# 6_ALARM.net
KiCad netlist of a schematic drawn in Altium Designer
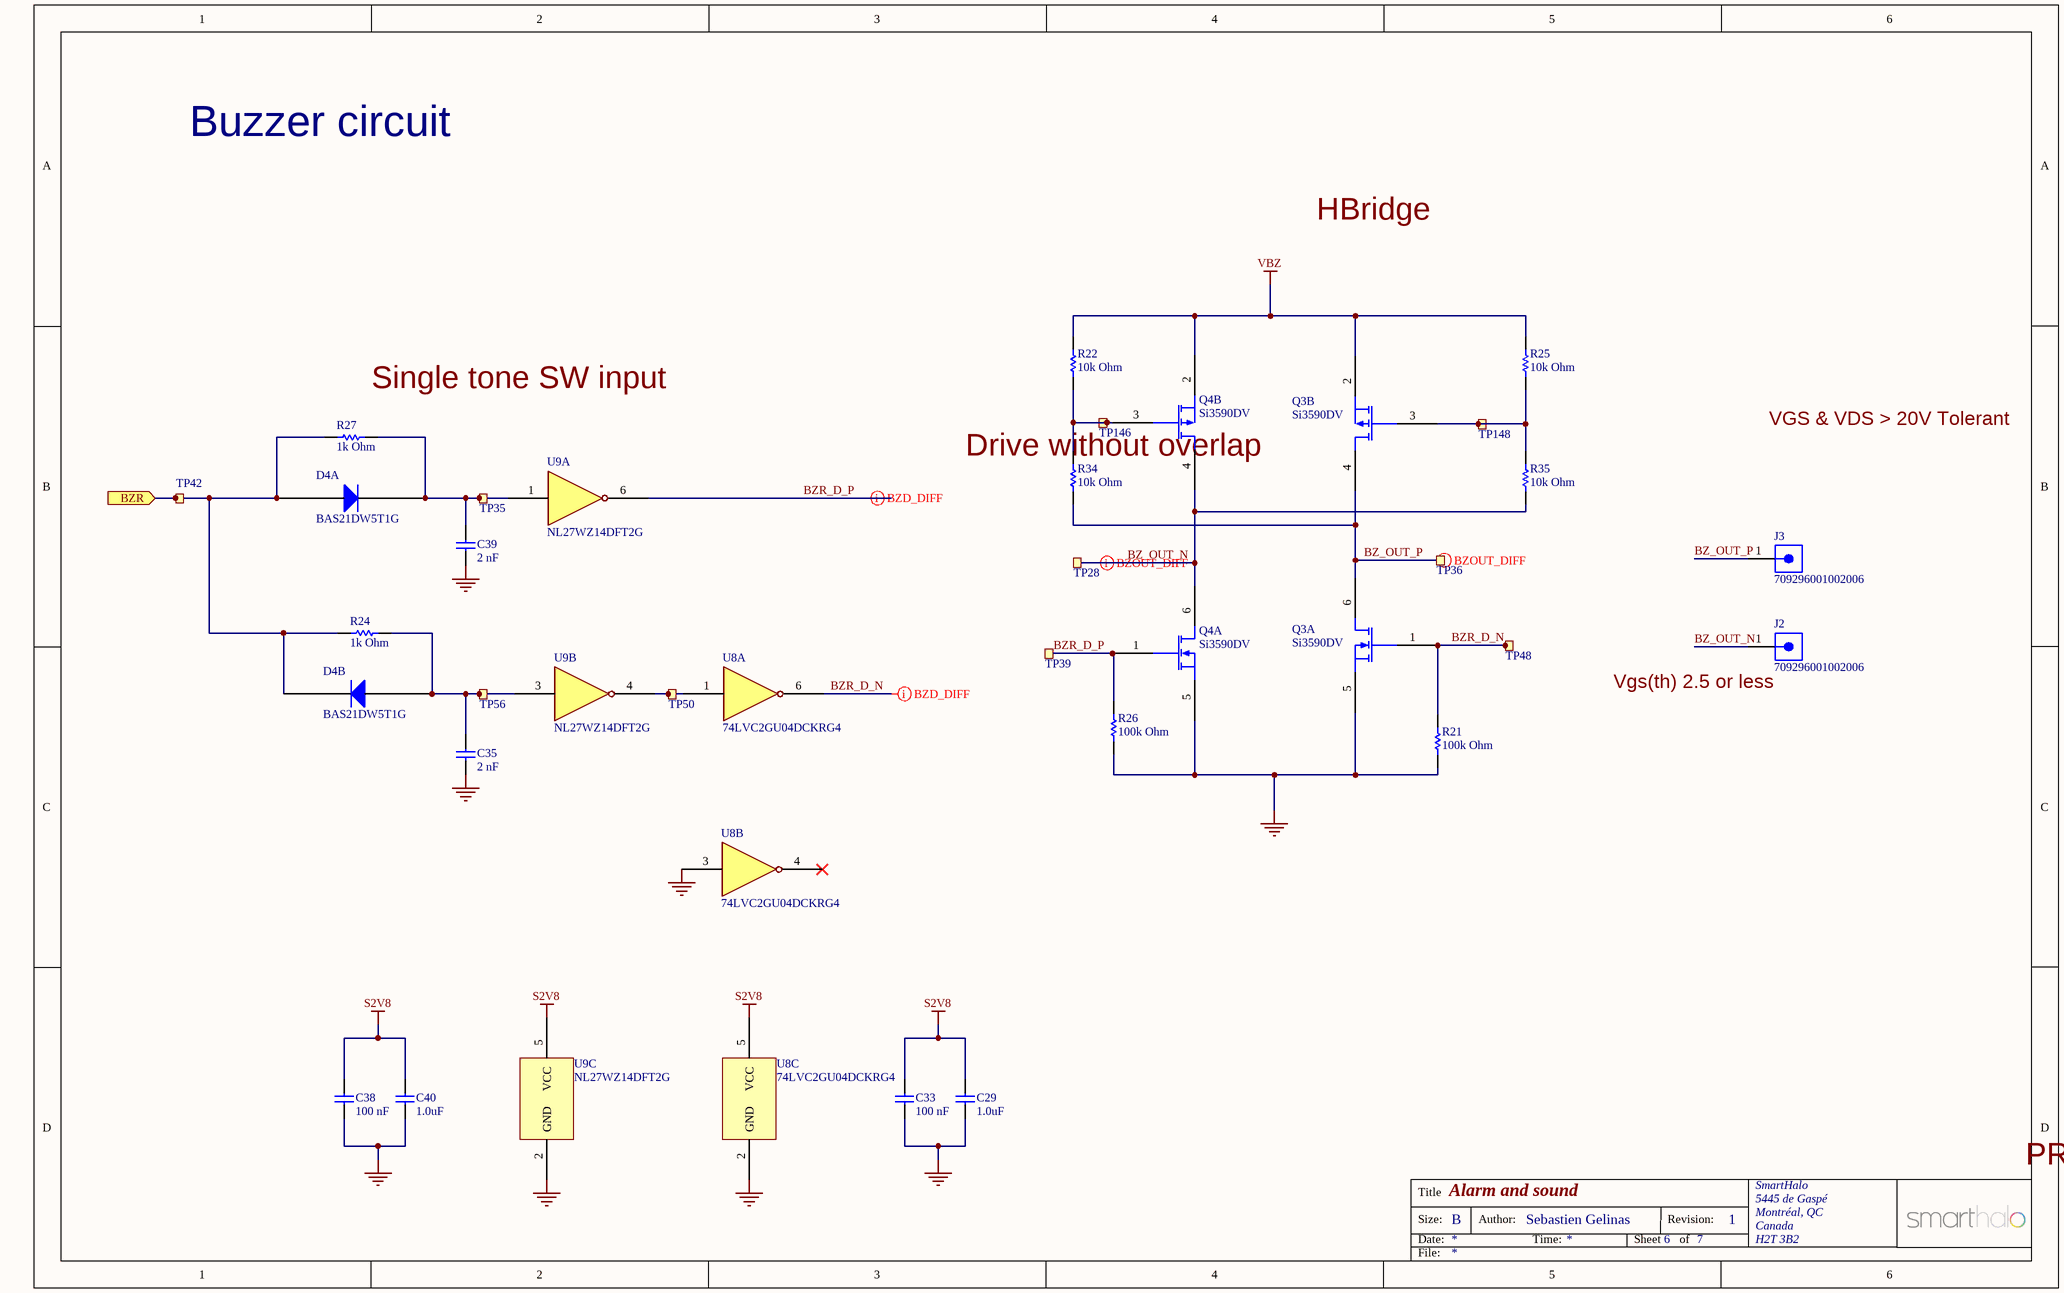
[diagram p0: 6_ALARM.SchDoc]

(export (version "E")
  (design (tool "Eeschema 10.0.6"))
  (components
    (comp (ref "C29")
      (value "1.0uF")
      (footprint "Varitron_CAP0603")
      (description "1uF 10V X7R 10% 0603 (1608 Metric)  SMD")
      (fields (field (name "TOLERANCE") "10%"))
      (libsource (lib "SmartHalo") (part "Varitron_CAP0603"))
    )
    (comp (ref "C33")
      (value "100 nF")
      (footprint "Varitron_CAP0402")
      (description "100 nF 10V X7R 10% 0402 (1005 Metric)  SMD")
      (fields (field (name "TOLERANCE") "10%"))
      (libsource (lib "SmartHalo") (part "Varitron_CAP0402"))
    )
    (comp (ref "C35")
      (value "2 nF")
      (footprint "Varitron_CAP0402")
      (description "2 nF 6V X5R 10% 0402 (1005 Metric)  SMD")
      (fields (field (name "TOLERANCE") "10%"))
      (libsource (lib "SmartHalo") (part "Varitron_CAP0402"))
    )
    (comp (ref "C38")
      (value "100 nF")
      (footprint "Varitron_CAP0402")
      (description "100 nF 10V X7R 10% 0402 (1005 Metric)  SMD")
      (fields (field (name "TOLERANCE") "10%"))
      (libsource (lib "SmartHalo") (part "Varitron_CAP0402"))
    )
    (comp (ref "C39")
      (value "2 nF")
      (footprint "Varitron_CAP0402")
      (description "2 nF 6V X5R 10% 0402 (1005 Metric)  SMD")
      (fields (field (name "TOLERANCE") "10%"))
      (libsource (lib "SmartHalo") (part "Varitron_CAP0402"))
    )
    (comp (ref "C40")
      (value "1.0uF")
      (footprint "Varitron_CAP0603")
      (description "1uF 10V X7R 10% 0603 (1608 Metric)  SMD")
      (fields (field (name "TOLERANCE") "10%"))
      (libsource (lib "SmartHalo") (part "Varitron_CAP0603"))
    )
    (comp (ref "D4")
      (value "BAS21DW5T1G")
      (footprint "SC70-5")
      (description "High Voltage Switching Diode")
      (fields (field (name "MANUFACTURER") "ON Semiconductor"))
      (libsource (lib "SmartHalo") (part "BAS21DW5T1G"))
    )
    (comp (ref "J2")
      (value "709296001002006")
      (footprint "709296001002006")
      (description "Connector, Single Horizontal Contact, 2 x 2 mm")
      (fields (field (name "MANUFACTURER") "AVX"))
      (libsource (lib "SmartHalo") (part "709296001002006"))
    )
    (comp (ref "J3")
      (value "709296001002006")
      (footprint "709296001002006")
      (description "Connector, Single Horizontal Contact, 2 x 2 mm")
      (fields (field (name "MANUFACTURER") "AVX"))
      (libsource (lib "SmartHalo") (part "709296001002006"))
    )
    (comp (ref "Q3")
      (value "Si3590DV")
      (footprint "TSOP-6")
      (description "N and P Channel 30 V MOSFET")
      (fields (field (name "MANUFACTURER") "Vishay"))
      (libsource (lib "SmartHalo") (part "Si3590DV"))
    )
    (comp (ref "Q4")
      (value "Si3590DV")
      (footprint "TSOP-6")
      (description "N and P Channel 30 V MOSFET")
      (fields (field (name "MANUFACTURER") "Vishay"))
      (libsource (lib "SmartHalo") (part "Si3590DV"))
    )
    (comp (ref "R21")
      (value "100k Ohm")
      (footprint "Varitron_RES0402")
      (description "100K 0.063W 5% 0402 (1005 Metric)  SMD")
      (fields (field (name "TOLERANCE") "5%") (field (name "POWER") "0.063W"))
      (libsource (lib "SmartHalo") (part "Varitron_RES0402"))
    )
    (comp (ref "R22")
      (value "10k Ohm")
      (footprint "Varitron_RES0402")
      (description "10K 0.063W 5% 0402 (1005 Metric)  SMD")
      (fields (field (name "TOLERANCE") "5%") (field (name "POWER") "0.063W"))
      (libsource (lib "SmartHalo") (part "Varitron_RES0402"))
    )
    (comp (ref "R24")
      (value "1k Ohm")
      (footprint "Varitron_RES0402")
      (description "1K 0.063W 5%  0402 (1005 Metric)  SMD")
      (fields (field (name "TOLERANCE") "5%") (field (name "POWER") "0.063W"))
      (libsource (lib "SmartHalo") (part "Varitron_RES0402"))
    )
    (comp (ref "R25")
      (value "10k Ohm")
      (footprint "Varitron_RES0402")
      (description "10K 0.063W 5% 0402 (1005 Metric)  SMD")
      (fields (field (name "TOLERANCE") "5%") (field (name "POWER") "0.063W"))
      (libsource (lib "SmartHalo") (part "Varitron_RES0402"))
    )
    (comp (ref "R26")
      (value "100k Ohm")
      (footprint "Varitron_RES0402")
      (description "100K 0.063W 5% 0402 (1005 Metric)  SMD")
      (fields (field (name "TOLERANCE") "5%") (field (name "POWER") "0.063W"))
      (libsource (lib "SmartHalo") (part "Varitron_RES0402"))
    )
    (comp (ref "R27")
      (value "1k Ohm")
      (footprint "Varitron_RES0402")
      (description "1K 0.063W 5%  0402 (1005 Metric)  SMD")
      (fields (field (name "TOLERANCE") "5%") (field (name "POWER") "0.063W"))
      (libsource (lib "SmartHalo") (part "Varitron_RES0402"))
    )
    (comp (ref "R34")
      (value "10k Ohm")
      (footprint "Varitron_RES0402")
      (description "10K 0.063W 5% 0402 (1005 Metric)  SMD")
      (fields (field (name "TOLERANCE") "5%") (field (name "POWER") "0.063W"))
      (libsource (lib "SmartHalo") (part "Varitron_RES0402"))
    )
    (comp (ref "R35")
      (value "10k Ohm")
      (footprint "Varitron_RES0402")
      (description "10K 0.063W 5% 0402 (1005 Metric)  SMD")
      (fields (field (name "TOLERANCE") "5%") (field (name "POWER") "0.063W"))
      (libsource (lib "SmartHalo") (part "Varitron_RES0402"))
    )
    (comp (ref "TP28")
      (value "~")
      (footprint "TESTPAD-TH-1_5mm")
      (description "Testpoint, through hole, 1.5mm")
      (libsource (lib "") (part "TESTPAD_TH_1_5MM_1"))
    )
    (comp (ref "TP35")
      (value "~")
      (footprint "TESTPAD-TH-35mils")
      (description "Testpoint, through hole, 35 mils")
      (libsource (lib "SmartHalo") (part "TESTPAD_TH_35mils"))
    )
    (comp (ref "TP36")
      (value "~")
      (footprint "TESTPAD-TH-1_5mm")
      (description "Testpoint, through hole, 1.5mm")
      (libsource (lib "SmartHalo") (part "TESTPAD_TH_1_5MM"))
    )
    (comp (ref "TP39")
      (value "~")
      (footprint "TESTPAD-TH-35mils")
      (description "Testpoint, through hole, 35 mils")
      (libsource (lib "") (part "TESTPAD_TH_35mils_1"))
    )
    (comp (ref "TP42")
      (value "~")
      (footprint "TESTPAD-TH-35mils")
      (description "Testpoint, through hole, 35 mils")
      (libsource (lib "SmartHalo") (part "TESTPAD_TH_35mils"))
    )
    (comp (ref "TP48")
      (value "~")
      (footprint "TESTPAD-TH-35mils")
      (description "Testpoint, through hole, 35 mils")
      (libsource (lib "SmartHalo") (part "TESTPAD_TH_35mils"))
    )
    (comp (ref "TP50")
      (value "~")
      (footprint "TESTPAD-TH-35mils")
      (description "Testpoint, through hole, 35 mils")
      (libsource (lib "SmartHalo") (part "TESTPAD_TH_35mils"))
    )
    (comp (ref "TP56")
      (value "~")
      (footprint "TESTPAD-TH-35mils")
      (description "Testpoint, through hole, 35 mils")
      (libsource (lib "SmartHalo") (part "TESTPAD_TH_35mils"))
    )
    (comp (ref "TP146")
      (value "TP")
      (footprint "TESTPAD-TH-35mils")
      (description "Testpoint, through hole, 35 mils")
      (libsource (lib "") (part "TESTPAD_TH_35mils_1"))
    )
    (comp (ref "TP148")
      (value "TP")
      (footprint "TESTPAD-TH-35mils")
      (description "Testpoint, through hole, 35 mils")
      (libsource (lib "SmartHalo") (part "TESTPAD_TH_35mils"))
    )
    (comp (ref "U8")
      (value "74LVC2GU04DCKRG4")
      (footprint "SOT363_SC70_6")
      (description "Dual Inverter Gate")
      (fields (field (name "MANUFACTURER") "Texas Instruments"))
      (libsource (lib "SmartHalo") (part "74LVC2GU04DCKRG4"))
    )
    (comp (ref "U9")
      (value "NL27WZ14DFT2G")
      (footprint "SOT363_SC70_6")
      (description "IC Dual Inverter with Schmitt Trigger Inputs")
      (fields (field (name "MANUFACTURER") "ON Semiconductor"))
      (libsource (lib "SmartHalo") (part "NL27WZ14DFT2G"))
    )
  )
  (nets
    (net (code "1") (name "/BZR") (class "Default")
      (node (ref "D4") (pin "1") (pinfunction "Anode_1") (pintype "passive"))
      (node (ref "D4") (pin "4") (pinfunction "Cathode_4") (pintype "passive"))
      (node (ref "R24") (pin "2") (pinfunction "2_2") (pintype "passive"))
      (node (ref "R27") (pin "2") (pinfunction "2_2") (pintype "passive"))
      (node (ref "TP42") (pin "1") (pinfunction "1_1") (pintype "passive"))
    )
    (net (code "2") (name "/BZR_D_N") (class "Default")
      (node (ref "Q3") (pin "1") (pinfunction "G1_1") (pintype "passive"))
      (node (ref "R21") (pin "2") (pinfunction "2_2") (pintype "passive"))
      (node (ref "TP48") (pin "1") (pinfunction "1_1") (pintype "passive"))
      (node (ref "U8") (pin "6") (pinfunction "6_6") (pintype "passive"))
    )
    (net (code "3") (name "/BZR_D_P") (class "Default")
      (node (ref "Q4") (pin "1") (pinfunction "G1_1") (pintype "passive"))
      (node (ref "R26") (pin "2") (pinfunction "2_2") (pintype "passive"))
      (node (ref "TP39") (pin "1") (pinfunction "1_1") (pintype "passive"))
      (node (ref "U9") (pin "6") (pinfunction "6_6") (pintype "passive"))
    )
    (net (code "4") (name "/BZ_OUT_N") (class "Default")
      (node (ref "J2") (pin "1") (pinfunction "1_1") (pintype "passive"))
      (node (ref "Q4") (pin "4") (pinfunction "D2_4") (pintype "passive"))
      (node (ref "Q4") (pin "6") (pinfunction "D1_6") (pintype "passive"))
      (node (ref "R35") (pin "1") (pinfunction "1_1") (pintype "passive"))
      (node (ref "TP28") (pin "1") (pinfunction "1_1") (pintype "passive"))
    )
    (net (code "5") (name "/BZ_OUT_P") (class "Default")
      (node (ref "J3") (pin "1") (pinfunction "1_1") (pintype "passive"))
      (node (ref "Q3") (pin "4") (pinfunction "D2_4") (pintype "passive"))
      (node (ref "Q3") (pin "6") (pinfunction "D1_6") (pintype "passive"))
      (node (ref "R34") (pin "1") (pinfunction "1_1") (pintype "passive"))
      (node (ref "TP36") (pin "1") (pinfunction "1_1") (pintype "passive"))
    )
    (net (code "6") (name "GND") (class "Default")
      (node (ref "C29") (pin "2") (pinfunction "2_2") (pintype "passive"))
      (node (ref "C33") (pin "2") (pinfunction "2_2") (pintype "passive"))
      (node (ref "C35") (pin "2") (pinfunction "2_2") (pintype "passive"))
      (node (ref "C38") (pin "2") (pinfunction "2_2") (pintype "passive"))
      (node (ref "C39") (pin "2") (pinfunction "2_2") (pintype "passive"))
      (node (ref "C40") (pin "2") (pinfunction "2_2") (pintype "passive"))
      (node (ref "Q3") (pin "5") (pinfunction "S1_5") (pintype "passive"))
      (node (ref "Q4") (pin "5") (pinfunction "S1_5") (pintype "passive"))
      (node (ref "R21") (pin "1") (pinfunction "1_1") (pintype "passive"))
      (node (ref "R26") (pin "1") (pinfunction "1_1") (pintype "passive"))
      (node (ref "U8") (pin "2") (pinfunction "GND_2") (pintype "passive"))
      (node (ref "U8") (pin "3") (pinfunction "3_3") (pintype "passive"))
      (node (ref "U9") (pin "2") (pinfunction "GND_2") (pintype "passive"))
    )
    (net (code "7") (name "Net-(D4A-Cathode)") (class "Default")
      (node (ref "C39") (pin "1") (pinfunction "1_1") (pintype "passive"))
      (node (ref "D4") (pin "5") (pinfunction "Cathode_5") (pintype "passive"))
      (node (ref "R27") (pin "1") (pinfunction "1_1") (pintype "passive"))
      (node (ref "TP35") (pin "1") (pinfunction "1_1") (pintype "passive"))
      (node (ref "U9") (pin "1") (pinfunction "1_1") (pintype "passive"))
    )
    (net (code "8") (name "Net-(D4B-Anode)") (class "Default")
      (node (ref "C35") (pin "1") (pinfunction "1_1") (pintype "passive"))
      (node (ref "D4") (pin "3") (pinfunction "Anode_3") (pintype "passive"))
      (node (ref "R24") (pin "1") (pinfunction "1_1") (pintype "passive"))
      (node (ref "TP56") (pin "1") (pinfunction "1_1") (pintype "passive"))
      (node (ref "U9") (pin "3") (pinfunction "3_3") (pintype "passive"))
    )
    (net (code "9") (name "Net-(Q3B-G2)") (class "Default")
      (node (ref "Q3") (pin "3") (pinfunction "G2_3") (pintype "passive"))
      (node (ref "R25") (pin "1") (pinfunction "1_1") (pintype "passive"))
      (node (ref "R35") (pin "2") (pinfunction "2_2") (pintype "passive"))
      (node (ref "TP148") (pin "1") (pinfunction "1_1") (pintype "passive"))
    )
    (net (code "10") (name "Net-(Q4B-G2)") (class "Default")
      (node (ref "Q4") (pin "3") (pinfunction "G2_3") (pintype "passive"))
      (node (ref "R22") (pin "1") (pinfunction "1_1") (pintype "passive"))
      (node (ref "R34") (pin "2") (pinfunction "2_2") (pintype "passive"))
      (node (ref "TP146") (pin "1") (pinfunction "1_1") (pintype "passive"))
    )
    (net (code "11") (name "Net-(TP50-Pad1)") (class "Default")
      (node (ref "TP50") (pin "1") (pinfunction "1_1") (pintype "passive"))
      (node (ref "U8") (pin "1") (pinfunction "1_1") (pintype "passive"))
      (node (ref "U9") (pin "4") (pinfunction "4_4") (pintype "passive"))
    )
    (net (code "12") (name "S2V8") (class "Default")
      (node (ref "C29") (pin "1") (pinfunction "1_1") (pintype "passive"))
      (node (ref "C33") (pin "1") (pinfunction "1_1") (pintype "passive"))
      (node (ref "C38") (pin "1") (pinfunction "1_1") (pintype "passive"))
      (node (ref "C40") (pin "1") (pinfunction "1_1") (pintype "passive"))
      (node (ref "U8") (pin "5") (pinfunction "VCC_5") (pintype "passive"))
      (node (ref "U9") (pin "5") (pinfunction "VCC_5") (pintype "passive"))
    )
    (net (code "13") (name "VBZ") (class "Default")
      (node (ref "Q3") (pin "2") (pinfunction "S2_2") (pintype "passive"))
      (node (ref "Q4") (pin "2") (pinfunction "S2_2") (pintype "passive"))
      (node (ref "R22") (pin "2") (pinfunction "2_2") (pintype "passive"))
      (node (ref "R25") (pin "2") (pinfunction "2_2") (pintype "passive"))
    )
    (net (code "14") (name "unconnected-(D4-Pad2)") (class "Default")
      (node (ref "D4") (pin "2") (pinfunction "2_2") (pintype "passive"))
    )
    (net (code "15") (name "unconnected-(U8-Pad4)") (class "Default")
      (node (ref "U8") (pin "4") (pinfunction "4_4") (pintype "passive+no_connect"))
    )
  )
)
